# Audio_ADC.net
KiCad netlist of a schematic drawn in Altium Designer
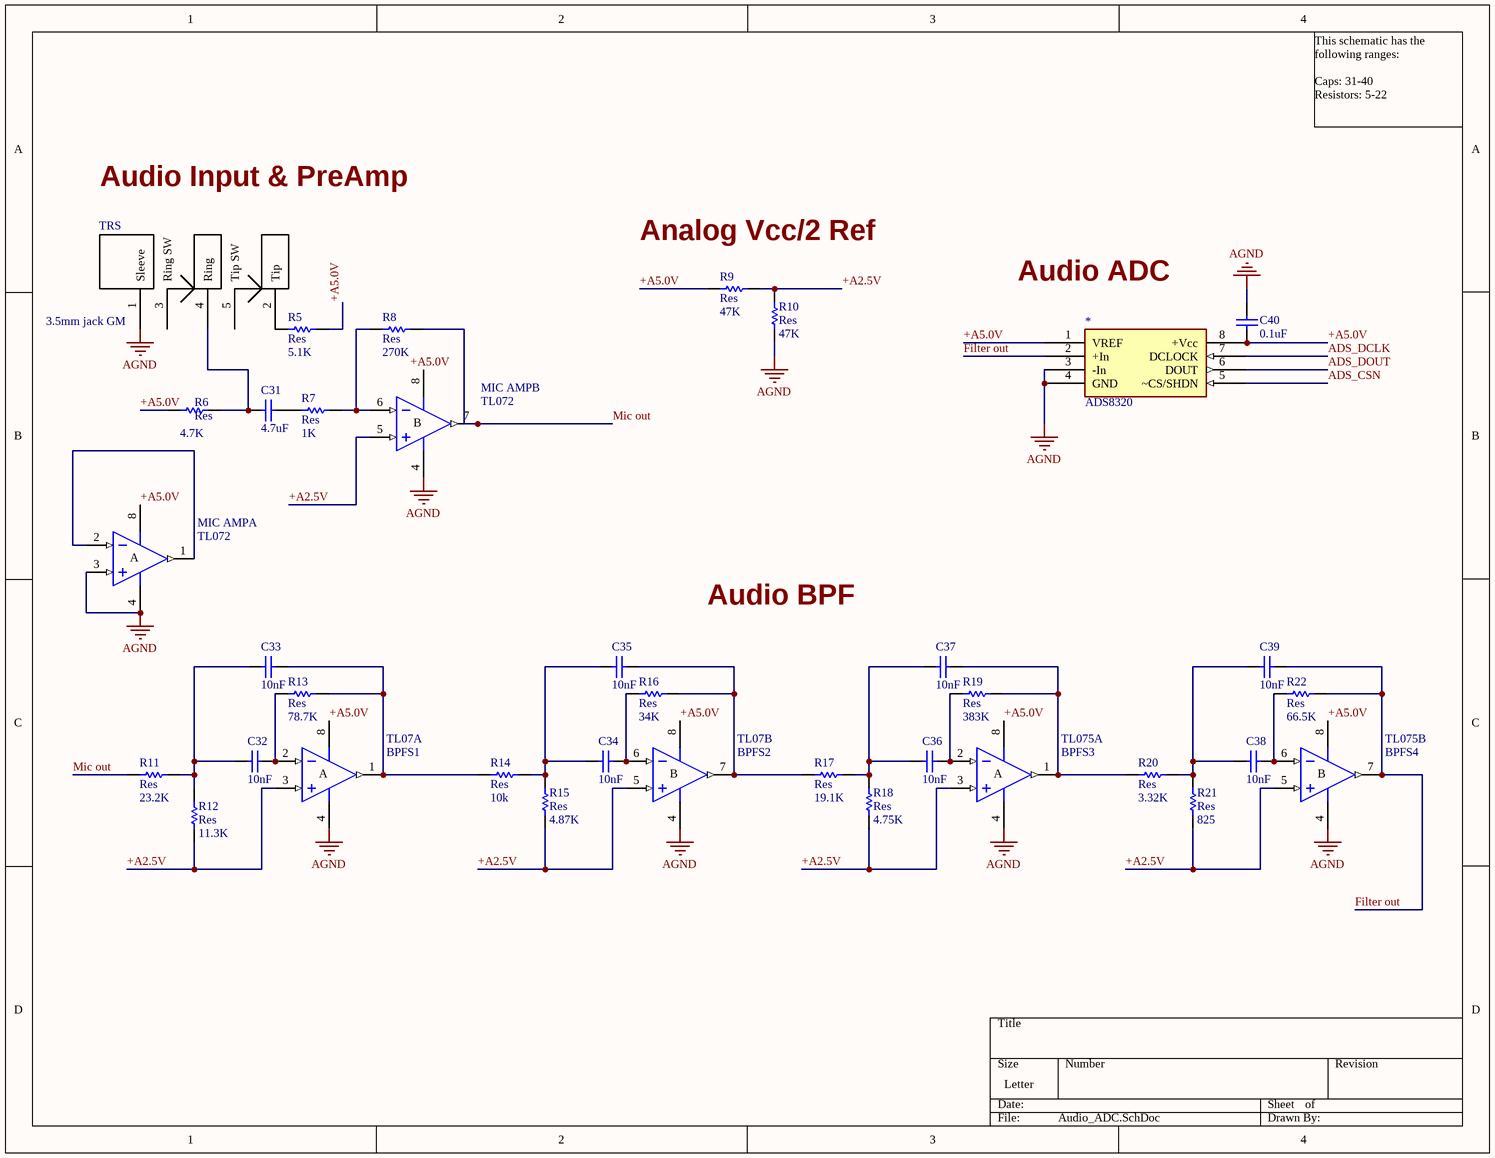
[diagram p0: Audio_ADC.SchDoc]

(export (version "E")
  (design (tool "Eeschema 10.0.6"))
  (components
    (comp (ref "*")
      (value "ADS8320")
      (footprint "TSOP65P490X110-8N")
      (libsource (lib "ADS8320") (part "ADS8320"))
    )
    (comp (ref "C31")
      (value "4.7uF")
      (footprint "0805")
      (description "Capacitor (Semiconductor SIM Model)")
      (fields (field (name "Comment") "Cap Semi") (field (name "PUBLISHER") "Altium Limited"))
      (libsource (lib "TMS320F28335GF") (part "Cap Semi"))
    )
    (comp (ref "C32")
      (value "10nF")
      (footprint "0805")
      (description "Capacitor (Semiconductor SIM Model)")
      (fields (field (name "Comment") "Cap Semi") (field (name "PUBLISHER") "Altium Limited"))
      (libsource (lib "TMS320F28335GF") (part "Cap Semi"))
    )
    (comp (ref "C33")
      (value "10nF")
      (footprint "0805")
      (description "Capacitor (Semiconductor SIM Model)")
      (fields (field (name "Comment") "Cap Semi") (field (name "PUBLISHER") "Altium Limited"))
      (libsource (lib "TMS320F28335GF") (part "Cap Semi"))
    )
    (comp (ref "C34")
      (value "10nF")
      (footprint "0805")
      (description "Capacitor (Semiconductor SIM Model)")
      (fields (field (name "Comment") "Cap Semi") (field (name "PUBLISHER") "Altium Limited"))
      (libsource (lib "TMS320F28335GF") (part "Cap Semi"))
    )
    (comp (ref "C35")
      (value "10nF")
      (footprint "0805")
      (description "Capacitor (Semiconductor SIM Model)")
      (fields (field (name "Comment") "Cap Semi") (field (name "PUBLISHER") "Altium Limited"))
      (libsource (lib "TMS320F28335GF") (part "Cap Semi"))
    )
    (comp (ref "C36")
      (value "10nF")
      (footprint "0805")
      (description "Capacitor (Semiconductor SIM Model)")
      (fields (field (name "Comment") "Cap Semi") (field (name "PUBLISHER") "Altium Limited"))
      (libsource (lib "TMS320F28335GF") (part "Cap Semi"))
    )
    (comp (ref "C37")
      (value "10nF")
      (footprint "0805")
      (description "Capacitor (Semiconductor SIM Model)")
      (fields (field (name "Comment") "Cap Semi") (field (name "PUBLISHER") "Altium Limited"))
      (libsource (lib "TMS320F28335GF") (part "Cap Semi"))
    )
    (comp (ref "C38")
      (value "10nF")
      (footprint "0805")
      (description "Capacitor (Semiconductor SIM Model)")
      (fields (field (name "Comment") "Cap Semi") (field (name "PUBLISHER") "Altium Limited"))
      (libsource (lib "TMS320F28335GF") (part "Cap Semi"))
    )
    (comp (ref "C39")
      (value "10nF")
      (footprint "0805")
      (description "Capacitor (Semiconductor SIM Model)")
      (fields (field (name "Comment") "Cap Semi") (field (name "PUBLISHER") "Altium Limited"))
      (libsource (lib "TMS320F28335GF") (part "Cap Semi"))
    )
    (comp (ref "C40")
      (value "0.1uF")
      (footprint "0805")
      (description "Capacitor (Semiconductor SIM Model)")
      (fields (field (name "Comment") "Cap Semi") (field (name "PUBLISHER") "Altium Limited"))
      (libsource (lib "TMS320F28335GF") (part "Cap Semi"))
    )
    (comp (ref "MIC AMP")
      (value "TL072")
      (footprint "DIP-8")
      (description "45MHz, 45V/µs, Dual Rail-to-Rail Input and Output Precision Operational Amplifier")
      (fields (field (name "PUBLISHER") "Altium Limited"))
      (libsource (lib "ECE LIB new") (part "LT1632CN8"))
    )
    (comp (ref "R5")
      (value "Res")
      (footprint "0805")
      (description "Semiconductor Resistor")
      (fields (field (name "ALTIUM_VALUE") "5.1K") (field (name "PUBLISHER") "Altium Limited"))
      (libsource (lib "TMS320F28335GF") (part "Res Semi"))
    )
    (comp (ref "R6")
      (value "Res")
      (footprint "0805")
      (description "Semiconductor Resistor")
      (fields (field (name "ALTIUM_VALUE") "4.7K") (field (name "PUBLISHER") "Altium Limited"))
      (libsource (lib "TMS320F28335GF") (part "Res Semi"))
    )
    (comp (ref "R7")
      (value "Res")
      (footprint "0805")
      (description "Semiconductor Resistor")
      (fields (field (name "ALTIUM_VALUE") "1K") (field (name "PUBLISHER") "Altium Limited"))
      (libsource (lib "TMS320F28335GF") (part "Res Semi"))
    )
    (comp (ref "R8")
      (value "Res")
      (footprint "0805")
      (description "Semiconductor Resistor")
      (fields (field (name "ALTIUM_VALUE") "270K") (field (name "PUBLISHER") "Altium Limited"))
      (libsource (lib "TMS320F28335GF") (part "Res Semi"))
    )
    (comp (ref "R9")
      (value "Res")
      (footprint "0805")
      (description "Semiconductor Resistor")
      (fields (field (name "ALTIUM_VALUE") "47K") (field (name "PUBLISHER") "Altium Limited"))
      (libsource (lib "TMS320F28335GF") (part "Res Semi"))
    )
    (comp (ref "R10")
      (value "Res")
      (footprint "0805")
      (description "Semiconductor Resistor")
      (fields (field (name "ALTIUM_VALUE") "47K") (field (name "PUBLISHER") "Altium Limited"))
      (libsource (lib "TMS320F28335GF") (part "Res Semi"))
    )
    (comp (ref "R11")
      (value "Res")
      (footprint "0805")
      (description "Semiconductor Resistor")
      (fields (field (name "ALTIUM_VALUE") "23.2K") (field (name "PUBLISHER") "Altium Limited"))
      (libsource (lib "TMS320F28335GF") (part "Res Semi"))
    )
    (comp (ref "R12")
      (value "Res")
      (footprint "0805")
      (description "Semiconductor Resistor")
      (fields (field (name "ALTIUM_VALUE") "11.3K") (field (name "PUBLISHER") "Altium Limited"))
      (libsource (lib "TMS320F28335GF") (part "Res Semi"))
    )
    (comp (ref "R13")
      (value "Res")
      (footprint "0805")
      (description "Semiconductor Resistor")
      (fields (field (name "ALTIUM_VALUE") "78.7K") (field (name "PUBLISHER") "Altium Limited"))
      (libsource (lib "TMS320F28335GF") (part "Res Semi"))
    )
    (comp (ref "R14")
      (value "Res")
      (footprint "0805")
      (description "Semiconductor Resistor")
      (fields (field (name "ALTIUM_VALUE") "10k") (field (name "PUBLISHER") "Altium Limited"))
      (libsource (lib "TMS320F28335GF") (part "Res Semi"))
    )
    (comp (ref "R15")
      (value "Res")
      (footprint "0805")
      (description "Semiconductor Resistor")
      (fields (field (name "ALTIUM_VALUE") "4.87K") (field (name "PUBLISHER") "Altium Limited"))
      (libsource (lib "TMS320F28335GF") (part "Res Semi"))
    )
    (comp (ref "R16")
      (value "Res")
      (footprint "0805")
      (description "Semiconductor Resistor")
      (fields (field (name "ALTIUM_VALUE") "34K") (field (name "PUBLISHER") "Altium Limited"))
      (libsource (lib "TMS320F28335GF") (part "Res Semi"))
    )
    (comp (ref "R17")
      (value "Res")
      (footprint "0805")
      (description "Semiconductor Resistor")
      (fields (field (name "ALTIUM_VALUE") "19.1K") (field (name "PUBLISHER") "Altium Limited"))
      (libsource (lib "TMS320F28335GF") (part "Res Semi"))
    )
    (comp (ref "R18")
      (value "Res")
      (footprint "0805")
      (description "Semiconductor Resistor")
      (fields (field (name "ALTIUM_VALUE") "4.75K") (field (name "PUBLISHER") "Altium Limited"))
      (libsource (lib "TMS320F28335GF") (part "Res Semi"))
    )
    (comp (ref "R19")
      (value "Res")
      (footprint "0805")
      (description "Semiconductor Resistor")
      (fields (field (name "ALTIUM_VALUE") "383K") (field (name "PUBLISHER") "Altium Limited"))
      (libsource (lib "TMS320F28335GF") (part "Res Semi"))
    )
    (comp (ref "R20")
      (value "Res")
      (footprint "0805")
      (description "Semiconductor Resistor")
      (fields (field (name "ALTIUM_VALUE") "3.32K") (field (name "PUBLISHER") "Altium Limited"))
      (libsource (lib "TMS320F28335GF") (part "Res Semi"))
    )
    (comp (ref "R21")
      (value "Res")
      (footprint "0805")
      (description "Semiconductor Resistor")
      (fields (field (name "ALTIUM_VALUE") "825") (field (name "PUBLISHER") "Altium Limited"))
      (libsource (lib "TMS320F28335GF") (part "Res Semi"))
    )
    (comp (ref "R22")
      (value "Res")
      (footprint "0805")
      (description "Semiconductor Resistor")
      (fields (field (name "ALTIUM_VALUE") "66.5K") (field (name "PUBLISHER") "Altium Limited"))
      (libsource (lib "TMS320F28335GF") (part "Res Semi"))
    )
    (comp (ref "TL07")
      (value "BPFS2")
      (footprint "DIP-8")
      (description "45MHz, 45V/µs, Dual Rail-to-Rail Input and Output Precision Operational Amplifier")
      (fields (field (name "PUBLISHER") "Altium Limited"))
      (libsource (lib "ECE LIB new") (part "LT1632CN8"))
    )
    (comp (ref "TL075")
      (value "BPFS3")
      (footprint "DIP-8")
      (description "45MHz, 45V/µs, Dual Rail-to-Rail Input and Output Precision Operational Amplifier")
      (fields (field (name "PUBLISHER") "Altium Limited"))
      (libsource (lib "ECE LIB new") (part "LT1632CN8"))
    )
    (comp (ref "TRS")
      (value "3.5mm jack GM")
      (footprint "3.5mm jack GM")
      (libsource (lib "ECE LIB new") (part "3.5mm jack GM"))
    )
  )
  (nets
    (net (code "1") (name "/+A2.5V") (class "Default")
      (node (ref "MIC AMP") (pin "5") (pinfunction "IN+_5") (pintype "input"))
      (node (ref "R10") (pin "2") (pinfunction "2_2") (pintype "passive"))
      (node (ref "R12") (pin "2") (pinfunction "2_2") (pintype "passive"))
      (node (ref "R15") (pin "1") (pinfunction "1_1") (pintype "passive"))
      (node (ref "R18") (pin "1") (pinfunction "1_1") (pintype "passive"))
      (node (ref "R21") (pin "1") (pinfunction "1_1") (pintype "passive"))
      (node (ref "R9") (pin "1") (pinfunction "1_1") (pintype "passive"))
      (node (ref "TL07") (pin "3") (pinfunction "IN+_3") (pintype "input"))
      (node (ref "TL07") (pin "5") (pinfunction "IN+_5") (pintype "input"))
      (node (ref "TL075") (pin "3") (pinfunction "IN+_3") (pintype "input"))
      (node (ref "TL075") (pin "5") (pinfunction "IN+_5") (pintype "input"))
    )
    (net (code "2") (name "/+A5.0V") (class "Default")
      (node (ref "*") (pin "1") (pinfunction "VREF_1") (pintype "power_in"))
      (node (ref "*") (pin "8") (pinfunction "+Vcc_8") (pintype "power_in"))
      (node (ref "C40") (pin "1") (pinfunction "1_1") (pintype "passive"))
      (node (ref "MIC AMP") (pin "8") (pinfunction "V+_8") (pintype "power_in"))
      (node (ref "R5") (pin "1") (pinfunction "1_1") (pintype "passive"))
      (node (ref "R6") (pin "2") (pinfunction "2_2") (pintype "passive"))
      (node (ref "R9") (pin "2") (pinfunction "2_2") (pintype "passive"))
      (node (ref "TL07") (pin "8") (pinfunction "V+_8") (pintype "power_in"))
      (node (ref "TL075") (pin "8") (pinfunction "V+_8") (pintype "power_in"))
    )
    (net (code "3") (name "/ADS_CSN") (class "Default")
      (node (ref "*") (pin "5") (pinfunction "~CS/SHDN_5") (pintype "input"))
    )
    (net (code "4") (name "/ADS_DCLK") (class "Default")
      (node (ref "*") (pin "7") (pinfunction "DCLOCK_7") (pintype "input"))
    )
    (net (code "5") (name "/ADS_DOUT") (class "Default")
      (node (ref "*") (pin "6") (pinfunction "DOUT_6") (pintype "output"))
    )
    (net (code "6") (name "/Filter out") (class "Default")
      (node (ref "*") (pin "2") (pinfunction "+In_2") (pintype "power_in"))
      (node (ref "C39") (pin "2") (pinfunction "2_2") (pintype "passive"))
      (node (ref "R22") (pin "1") (pinfunction "1_1") (pintype "passive"))
      (node (ref "TL075") (pin "7") (pinfunction "OUT_7") (pintype "output"))
    )
    (net (code "7") (name "/Mic out") (class "Default")
      (node (ref "MIC AMP") (pin "7") (pinfunction "OUT_7") (pintype "output"))
      (node (ref "R11") (pin "2") (pinfunction "2_2") (pintype "passive"))
      (node (ref "R8") (pin "1") (pinfunction "1_1") (pintype "passive"))
    )
    (net (code "8") (name "AGND") (class "Default")
      (node (ref "*") (pin "3") (pinfunction "-In_3") (pintype "power_in"))
      (node (ref "*") (pin "4") (pinfunction "GND_4") (pintype "power_in"))
      (node (ref "C40") (pin "2") (pinfunction "2_2") (pintype "passive"))
      (node (ref "MIC AMP") (pin "3") (pinfunction "IN+_3") (pintype "input"))
      (node (ref "MIC AMP") (pin "4") (pinfunction "V-_4") (pintype "power_in"))
      (node (ref "R10") (pin "1") (pinfunction "1_1") (pintype "passive"))
      (node (ref "TL07") (pin "4") (pinfunction "V-_4") (pintype "power_in"))
      (node (ref "TL075") (pin "4") (pinfunction "V-_4") (pintype "power_in"))
      (node (ref "TRS") (pin "1") (pinfunction "Sleeve_1") (pintype "passive"))
    )
    (net (code "9") (name "Net-(C31-Pad2)") (class "Default")
      (node (ref "C31") (pin "2") (pinfunction "2_2") (pintype "passive"))
      (node (ref "R7") (pin "2") (pinfunction "2_2") (pintype "passive"))
    )
    (net (code "10") (name "Net-(C32-Pad1)") (class "Default")
      (node (ref "C32") (pin "1") (pinfunction "1_1") (pintype "passive"))
      (node (ref "C33") (pin "1") (pinfunction "1_1") (pintype "passive"))
      (node (ref "R11") (pin "1") (pinfunction "1_1") (pintype "passive"))
      (node (ref "R12") (pin "1") (pinfunction "1_1") (pintype "passive"))
    )
    (net (code "11") (name "Net-(C34-Pad1)") (class "Default")
      (node (ref "C34") (pin "1") (pinfunction "1_1") (pintype "passive"))
      (node (ref "C35") (pin "1") (pinfunction "1_1") (pintype "passive"))
      (node (ref "R14") (pin "1") (pinfunction "1_1") (pintype "passive"))
      (node (ref "R15") (pin "2") (pinfunction "2_2") (pintype "passive"))
    )
    (net (code "12") (name "Net-(C36-Pad1)") (class "Default")
      (node (ref "C36") (pin "1") (pinfunction "1_1") (pintype "passive"))
      (node (ref "C37") (pin "1") (pinfunction "1_1") (pintype "passive"))
      (node (ref "R17") (pin "1") (pinfunction "1_1") (pintype "passive"))
      (node (ref "R18") (pin "2") (pinfunction "2_2") (pintype "passive"))
    )
    (net (code "13") (name "Net-(C38-Pad1)") (class "Default")
      (node (ref "C38") (pin "1") (pinfunction "1_1") (pintype "passive"))
      (node (ref "C39") (pin "1") (pinfunction "1_1") (pintype "passive"))
      (node (ref "R20") (pin "1") (pinfunction "1_1") (pintype "passive"))
      (node (ref "R21") (pin "2") (pinfunction "2_2") (pintype "passive"))
    )
    (net (code "14") (name "Net-(MIC AMPA-IN-)") (class "Default")
      (node (ref "MIC AMP") (pin "1") (pinfunction "OUT_1") (pintype "output"))
      (node (ref "MIC AMP") (pin "2") (pinfunction "IN-_2") (pintype "input"))
    )
    (net (code "15") (name "Net-(MIC AMPB-IN-)") (class "Default")
      (node (ref "MIC AMP") (pin "6") (pinfunction "IN-_6") (pintype "input"))
      (node (ref "R7") (pin "1") (pinfunction "1_1") (pintype "passive"))
      (node (ref "R8") (pin "2") (pinfunction "2_2") (pintype "passive"))
    )
    (net (code "16") (name "Net-(TL07A-IN-)") (class "Default")
      (node (ref "C32") (pin "2") (pinfunction "2_2") (pintype "passive"))
      (node (ref "R13") (pin "2") (pinfunction "2_2") (pintype "passive"))
      (node (ref "TL07") (pin "2") (pinfunction "IN-_2") (pintype "input"))
    )
    (net (code "17") (name "Net-(TL07A-OUT)") (class "Default")
      (node (ref "C33") (pin "2") (pinfunction "2_2") (pintype "passive"))
      (node (ref "R13") (pin "1") (pinfunction "1_1") (pintype "passive"))
      (node (ref "R14") (pin "2") (pinfunction "2_2") (pintype "passive"))
      (node (ref "TL07") (pin "1") (pinfunction "OUT_1") (pintype "output"))
    )
    (net (code "18") (name "Net-(TL07B-IN-)") (class "Default")
      (node (ref "C34") (pin "2") (pinfunction "2_2") (pintype "passive"))
      (node (ref "R16") (pin "2") (pinfunction "2_2") (pintype "passive"))
      (node (ref "TL07") (pin "6") (pinfunction "IN-_6") (pintype "input"))
    )
    (net (code "19") (name "Net-(TL07B-OUT)") (class "Default")
      (node (ref "C35") (pin "2") (pinfunction "2_2") (pintype "passive"))
      (node (ref "R16") (pin "1") (pinfunction "1_1") (pintype "passive"))
      (node (ref "R17") (pin "2") (pinfunction "2_2") (pintype "passive"))
      (node (ref "TL07") (pin "7") (pinfunction "OUT_7") (pintype "output"))
    )
    (net (code "20") (name "Net-(TL075A-IN-)") (class "Default")
      (node (ref "C36") (pin "2") (pinfunction "2_2") (pintype "passive"))
      (node (ref "R19") (pin "2") (pinfunction "2_2") (pintype "passive"))
      (node (ref "TL075") (pin "2") (pinfunction "IN-_2") (pintype "input"))
    )
    (net (code "21") (name "Net-(TL075A-OUT)") (class "Default")
      (node (ref "C37") (pin "2") (pinfunction "2_2") (pintype "passive"))
      (node (ref "R19") (pin "1") (pinfunction "1_1") (pintype "passive"))
      (node (ref "R20") (pin "2") (pinfunction "2_2") (pintype "passive"))
      (node (ref "TL075") (pin "1") (pinfunction "OUT_1") (pintype "output"))
    )
    (net (code "22") (name "Net-(TL075B-IN-)") (class "Default")
      (node (ref "C38") (pin "2") (pinfunction "2_2") (pintype "passive"))
      (node (ref "R22") (pin "2") (pinfunction "2_2") (pintype "passive"))
      (node (ref "TL075") (pin "6") (pinfunction "IN-_6") (pintype "input"))
    )
    (net (code "23") (name "Net-(TRS-Ring)") (class "Default")
      (node (ref "C31") (pin "1") (pinfunction "1_1") (pintype "passive"))
      (node (ref "R6") (pin "1") (pinfunction "1_1") (pintype "passive"))
      (node (ref "TRS") (pin "4") (pinfunction "Ring_4") (pintype "passive"))
    )
    (net (code "24") (name "Net-(TRS-Tip)") (class "Default")
      (node (ref "R5") (pin "2") (pinfunction "2_2") (pintype "passive"))
      (node (ref "TRS") (pin "2") (pinfunction "Tip_2") (pintype "passive"))
    )
    (net (code "25") (name "unconnected-(MIC AMPB-V+-Pad8)") (class "Default")
      (node (ref "MIC AMP") (pin "8") (pinfunction "V+_8") (pintype "power_in"))
    )
    (net (code "26") (name "unconnected-(TRS-Ring_SW-Pad3)") (class "Default")
      (node (ref "TRS") (pin "3") (pinfunction "Ring_SW_3") (pintype "passive"))
    )
    (net (code "27") (name "unconnected-(TRS-Tip_SW-Pad5)") (class "Default")
      (node (ref "TRS") (pin "5") (pinfunction "Tip_SW_5") (pintype "passive"))
    )
  )
)
